# MCU.net
KiCad netlist of a schematic drawn in Altium Designer
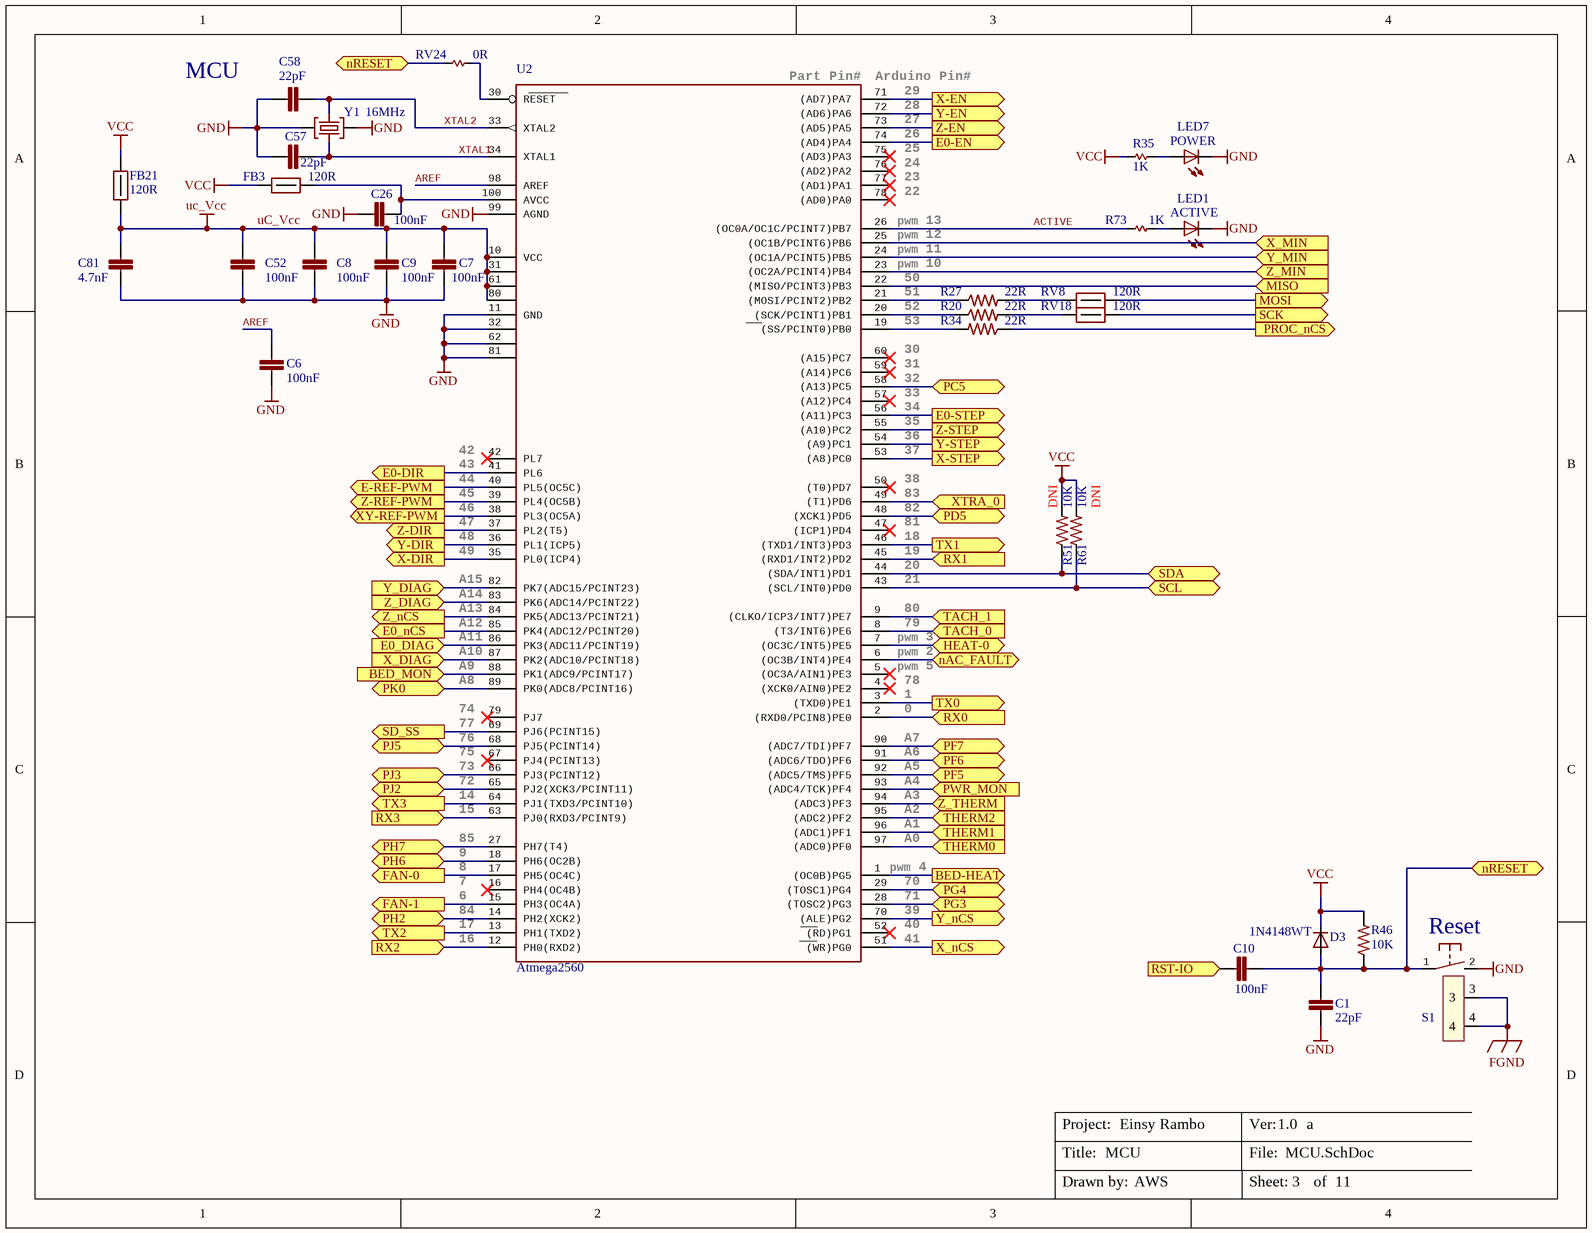
[diagram p0: MCU.SchDoc]

(export (version "E")
  (design (tool "Eeschema 10.0.6"))
  (components
    (comp (ref "C1")
      (value "22pF")
      (footprint "C0402")
      (description "CAP CER 0402 22pF 50V 5% C0G")
      (fields (field (name "MANUFACTURER") "AVX") (field (name "PART") "22pF 50V"))
      (libsource (lib "") (part "04025A220JAT2A_1"))
    )
    (comp (ref "C6")
      (value "100nF")
      (footprint "C0402")
      (description "CAP CER 0402 100nF 16V 10% X7R")
      (fields (field (name "MANUFACTURER") "Murata") (field (name "TOLERANCE") "+/- 10%"))
      (libsource (lib "3Delight") (part "GRM155R71C104KA88D"))
    )
    (comp (ref "C7")
      (value "100nF")
      (footprint "C0402")
      (description "CAP CER 0402 100nF 16V 10% X7R")
      (fields (field (name "MANUFACTURER") "Murata") (field (name "TOLERANCE") "+/- 10%"))
      (libsource (lib "3Delight") (part "GRM155R71C104KA88D"))
    )
    (comp (ref "C8")
      (value "100nF")
      (footprint "C0402")
      (description "CAP CER 0402 100nF 16V 10% X7R")
      (fields (field (name "MANUFACTURER") "Murata") (field (name "TOLERANCE") "+/- 10%"))
      (libsource (lib "3Delight") (part "GRM155R71C104KA88D"))
    )
    (comp (ref "C9")
      (value "100nF")
      (footprint "C0402")
      (description "CAP CER 0402 100nF 16V 10% X7R")
      (fields (field (name "MANUFACTURER") "Murata") (field (name "TOLERANCE") "+/- 10%"))
      (libsource (lib "3Delight") (part "GRM155R71C104KA88D"))
    )
    (comp (ref "C10")
      (value "100nF")
      (footprint "C0402")
      (description "CAP CER 0402 100nF 16V 10% X7R")
      (fields (field (name "MANUFACTURER") "Murata") (field (name "TOLERANCE") "+/- 10%"))
      (libsource (lib "") (part "GRM155R71C104KA88D_1"))
    )
    (comp (ref "C26")
      (value "100nF")
      (footprint "C0402")
      (description "CAP CER 0402 100nF 16V 10% X7R")
      (fields (field (name "MANUFACTURER") "Murata") (field (name "TOLERANCE") "+/- 10%"))
      (libsource (lib "") (part "GRM155R71C104KA88D_2"))
    )
    (comp (ref "C52")
      (value "100nF")
      (footprint "C0402")
      (description "CAP CER 0402 100nF 16V 10% X7R")
      (fields (field (name "MANUFACTURER") "Murata") (field (name "TOLERANCE") "+/- 10%"))
      (libsource (lib "3Delight") (part "GRM155R71C104KA88D"))
    )
    (comp (ref "C57")
      (value "22pF")
      (footprint "C0402")
      (description "CAP CER 0402 22pF 50V 5% C0G")
      (fields (field (name "MANUFACTURER") "AVX") (field (name "PART") "22pF 50V"))
      (libsource (lib "3Delight") (part "04025A220JAT2A"))
    )
    (comp (ref "C58")
      (value "22pF")
      (footprint "C0402")
      (description "CAP CER 0402 22pF 50V 5% C0G")
      (fields (field (name "MANUFACTURER") "AVX") (field (name "PART") "22pF 50V"))
      (libsource (lib "3Delight") (part "04025A220JAT2A"))
    )
    (comp (ref "C81")
      (value "4.7nF")
      (footprint "C0402")
      (description "CAP CER 0402 4.7nF 25V 10% X7R")
      (fields (field (name "MANUFACTURER") "YAGEO") (field (name "TOLERANCE") "+/- 10%"))
      (libsource (lib "3Delight") (part "CC0402KRX7R8BB472"))
    )
    (comp (ref "D3")
      (value "1N4148WT")
      (footprint "SOD523")
      (description "DIODE SOD523")
      (fields (field (name "MANUFACTURER") "Fairchild") (field (name "TOLERANCE") "NA"))
      (libsource (lib "3Delight") (part "1N4148WT"))
    )
    (comp (ref "FB3")
      (value "120R")
      (footprint "FB0603")
      (description "FERRITE BEAD 120 OHM 0603 1LN")
      (fields (field (name "MANUFACTURER") "Samsung") (field (name "PART") "FERRITE 120R 3A 0603"))
      (libsource (lib "3Delight") (part "FERRITE 220R 2.5A 0603"))
    )
    (comp (ref "FB21")
      (value "120R")
      (footprint "FB0603")
      (description "FERRITE BEAD 120 OHM 0603 1LN")
      (fields (field (name "MANUFACTURER") "Samsung") (field (name "PART") "FERRITE 120R 3A 0603"))
      (libsource (lib "Inductors") (part "FERRITE 120R 3A 0603"))
    )
    (comp (ref "LED1")
      (value "YEL")
      (footprint "LED2012120")
      (description "LED 0805 Yellow")
      (fields (field (name "MANUFACTURER") "Dialight") (field (name "TOLERANCE") "NA"))
      (libsource (lib "3Delight") (part "5988140107F"))
    )
    (comp (ref "LED7")
      (value "GRN")
      (footprint "LED2012120")
      (description "LED 0805 Green")
      (fields (field (name "MANUFACTURER") "Dialight") (field (name "TOLERANCE") "NA"))
      (libsource (lib "3Delight") (part "5988170107F"))
    )
    (comp (ref "R20")
      (value "22R")
      (footprint "R0402")
      (description "RES 0402 22r 62.5mW 1%")
      (fields (field (name "MANUFACTURER") "Yageo") (field (name "TOLERANCE") "+/- 1%"))
      (libsource (lib "3Delight") (part "RC0402FR-0722RL"))
    )
    (comp (ref "R27")
      (value "22R")
      (footprint "R0402")
      (description "RES 0402 22r 62.5mW 1%")
      (fields (field (name "MANUFACTURER") "Yageo") (field (name "TOLERANCE") "+/- 1%"))
      (libsource (lib "3Delight") (part "RC0402FR-0722RL"))
    )
    (comp (ref "R34")
      (value "22R")
      (footprint "R0402")
      (description "RES 0402 22r 62.5mW 1%")
      (fields (field (name "MANUFACTURER") "Yageo") (field (name "TOLERANCE") "+/- 1%"))
      (libsource (lib "3Delight") (part "RC0402FR-0722RL"))
    )
    (comp (ref "R35")
      (value "1K")
      (footprint "R0402")
      (description "RES SMD 1K OHM 1% 1/16W 0402")
      (fields (field (name "MANUFACTURER") "Yageo") (field (name "PART") "1k"))
      (libsource (lib "3Delight") (part "RC0402FR-071KL"))
    )
    (comp (ref "R46")
      (value "10K")
      (footprint "R0402")
      (description "RES SMD 10K OHM 1% 1/16W 0402")
      (fields (field (name "MANUFACTURER") "Yageo") (field (name "PART") "10k 1% 0402"))
      (libsource (lib "3Delight") (part "RC0402FR-0710KP"))
    )
    (comp (ref "R51")
      (value "10K")
      (footprint "R0402")
      (description "RES SMD 10K OHM 1% 1/16W 0402")
      (fields
        (field (name "MANUFACTURER") "Yageo")
        (field (name "PART") "10k 1% 0402")
        (field (name "DNI") "DNI")
      )
      (libsource (lib "3Delight") (part "RC0402FR-0710KP"))
    )
    (comp (ref "R61")
      (value "10K")
      (footprint "R0402")
      (description "RES SMD 10K OHM 1% 1/16W 0402")
      (fields
        (field (name "MANUFACTURER") "Yageo")
        (field (name "PART") "10k 1% 0402")
        (field (name "DNI") "DNI")
      )
      (libsource (lib "3Delight") (part "RC0402FR-0710KP"))
    )
    (comp (ref "R73")
      (value "1K")
      (footprint "R0402")
      (description "RES SMD 1K OHM 1% 1/16W 0402")
      (fields (field (name "MANUFACTURER") "Yageo") (field (name "PART") "1k"))
      (libsource (lib "3Delight") (part "RC0402FR-071KL"))
    )
    (comp (ref "RV8")
      (value "120R")
      (footprint "R0402")
      (description "FERRITE BEAD 120 OHM 0402 1LN")
      (fields (field (name "MANUFACTURER") "Taiyo Yuden") (field (name "PART") "FERRITE 120R 1A 0402"))
      (libsource (lib "Inductors") (part "FERRITE 120R 1A 0402"))
    )
    (comp (ref "RV18")
      (value "120R")
      (footprint "R0402")
      (description "FERRITE BEAD 120 OHM 0402 1LN")
      (fields (field (name "MANUFACTURER") "Taiyo Yuden") (field (name "PART") "FERRITE 120R 1A 0402"))
      (libsource (lib "Inductors") (part "FERRITE 120R 1A 0402"))
    )
    (comp (ref "RV24")
      (value "0R")
      (footprint "R0402")
      (description "RES SMD 0.0OHM JUMPER 1/10W 0402")
      (fields (field (name "MANUFACTURER") "Panasonic") (field (name "TOLERANCE") "1%"))
      (libsource (lib "Resistors") (part "0R 0402"))
    )
    (comp (ref "S1")
      (value "1571610-2")
      (footprint "B3F-31XX")
      (description "SWTCH Momentary Washable")
      (fields (field (name "MANUFACTURER") "TE") (field (name "PART") "Tact PB R/A"))
      (libsource (lib "3Delight") (part "1571610-2"))
    )
    (comp (ref "U2")
      (value "Atmega2560")
      (footprint "TSQFP50P1600X1600X120-100L")
      (fields
        (field (name "MANUFACTURER") "Microchip")
        (field (name "PART") "ATMEGA2560")
        (field (name "TOLERANCE") "NA")
      )
      (libsource (lib "ICs-uC") (part "ATMEGA2560AU_SM"))
    )
    (comp (ref "Y1")
      (value "16MHz")
      (footprint "CRYS320250")
      (description "Crystal 16mHz 10ppm 10pF")
      (fields (field (name "MANUFACTURER") "TXC") (field (name "TOLERANCE") "10ppm"))
      (libsource (lib "3Delight") (part "7M-16.000MEEQ-T"))
    )
  )
  (nets
    (net (code "1") (name "/ACTIVE") (class "Default")
      (node (ref "R73") (pin "2") (pinfunction "2_2") (pintype "passive"))
      (node (ref "U2") (pin "26") (pinfunction "(OC0A/OC1C/PCINT7)PB7_26") (pintype "passive"))
    )
    (net (code "2") (name "/AREF") (class "Default")
      (node (ref "C6") (pin "1") (pinfunction "1_1") (pintype "passive"))
      (node (ref "U2") (pin "98") (pinfunction "AREF_98") (pintype "passive"))
    )
    (net (code "3") (name "/BED-HEAT") (class "Default")
      (node (ref "U2") (pin "1") (pinfunction "(OC0B)PG5_1") (pintype "passive"))
    )
    (net (code "4") (name "/BED_MON") (class "Default")
      (node (ref "U2") (pin "88") (pinfunction "PK1(ADC9/PCINT17)_88") (pintype "passive"))
    )
    (net (code "5") (name "/E-REF-PWM") (class "Default")
      (node (ref "U2") (pin "40") (pinfunction "PL5(OC5C)_40") (pintype "passive"))
    )
    (net (code "6") (name "/E0-DIR") (class "Default")
      (node (ref "U2") (pin "41") (pinfunction "PL6_41") (pintype "passive"))
    )
    (net (code "7") (name "/E0-EN") (class "Default")
      (node (ref "U2") (pin "74") (pinfunction "(AD4)PA4_74") (pintype "passive"))
    )
    (net (code "8") (name "/E0-STEP") (class "Default")
      (node (ref "U2") (pin "56") (pinfunction "(A11)PC3_56") (pintype "passive"))
    )
    (net (code "9") (name "/E0_DIAG") (class "Default")
      (node (ref "U2") (pin "86") (pinfunction "PK3(ADC11/PCINT19)_86") (pintype "passive"))
    )
    (net (code "10") (name "/E0_nCS") (class "Default")
      (node (ref "U2") (pin "85") (pinfunction "PK4(ADC12/PCINT20)_85") (pintype "passive"))
    )
    (net (code "11") (name "/FAN-0") (class "Default")
      (node (ref "U2") (pin "17") (pinfunction "PH5(OC4C)_17") (pintype "passive"))
    )
    (net (code "12") (name "/FAN-1") (class "Default")
      (node (ref "U2") (pin "15") (pinfunction "PH3(OC4A)_15") (pintype "passive"))
    )
    (net (code "13") (name "/HEAT-0") (class "Default")
      (node (ref "U2") (pin "7") (pinfunction "(OC3C/INT5)PE5_7") (pintype "passive"))
    )
    (net (code "14") (name "/MISO") (class "Default")
      (node (ref "U2") (pin "22") (pinfunction "(MISO/PCINT3)PB3_22") (pintype "passive"))
    )
    (net (code "15") (name "/MOSI") (class "Default")
      (node (ref "RV8") (pin "2") (pinfunction "2_2") (pintype "passive"))
    )
    (net (code "16") (name "/PC5") (class "Default")
      (node (ref "U2") (pin "58") (pinfunction "(A13)PC5_58") (pintype "passive"))
    )
    (net (code "17") (name "/PD5") (class "Default")
      (node (ref "U2") (pin "48") (pinfunction "(XCK1)PD5_48") (pintype "passive"))
    )
    (net (code "18") (name "/PF5") (class "Default")
      (node (ref "U2") (pin "92") (pinfunction "(ADC5/TMS)PF5_92") (pintype "passive"))
    )
    (net (code "19") (name "/PF6") (class "Default")
      (node (ref "U2") (pin "91") (pinfunction "(ADC6/TDO)PF6_91") (pintype "passive"))
    )
    (net (code "20") (name "/PF7") (class "Default")
      (node (ref "U2") (pin "90") (pinfunction "(ADC7/TDI)PF7_90") (pintype "passive"))
    )
    (net (code "21") (name "/PG3") (class "Default")
      (node (ref "U2") (pin "28") (pinfunction "(TOSC2)PG3_28") (pintype "passive"))
    )
    (net (code "22") (name "/PG4") (class "Default")
      (node (ref "U2") (pin "29") (pinfunction "(TOSC1)PG4_29") (pintype "passive"))
    )
    (net (code "23") (name "/PH2") (class "Default")
      (node (ref "U2") (pin "14") (pinfunction "PH2(XCK2)_14") (pintype "passive"))
    )
    (net (code "24") (name "/PH6") (class "Default")
      (node (ref "U2") (pin "18") (pinfunction "PH6(OC2B)_18") (pintype "passive"))
    )
    (net (code "25") (name "/PH7") (class "Default")
      (node (ref "U2") (pin "27") (pinfunction "PH7(T4)_27") (pintype "passive"))
    )
    (net (code "26") (name "/PJ2") (class "Default")
      (node (ref "U2") (pin "65") (pinfunction "PJ2(XCK3/PCINT11)_65") (pintype "passive"))
    )
    (net (code "27") (name "/PJ3") (class "Default")
      (node (ref "U2") (pin "66") (pinfunction "PJ3(PCINT12)_66") (pintype "passive"))
    )
    (net (code "28") (name "/PJ5") (class "Default")
      (node (ref "U2") (pin "68") (pinfunction "PJ5(PCINT14)_68") (pintype "passive"))
    )
    (net (code "29") (name "/PK0") (class "Default")
      (node (ref "U2") (pin "89") (pinfunction "PK0(ADC8/PCINT16)_89") (pintype "passive"))
    )
    (net (code "30") (name "/PROC_nCS") (class "Default")
      (node (ref "R34") (pin "1") (pinfunction "1_1") (pintype "passive"))
    )
    (net (code "31") (name "/PWR_MON") (class "Default")
      (node (ref "U2") (pin "93") (pinfunction "(ADC4/TCK)PF4_93") (pintype "passive"))
    )
    (net (code "32") (name "/RST-IO") (class "Default")
      (node (ref "C10") (pin "1") (pinfunction "1_1") (pintype "passive"))
    )
    (net (code "33") (name "/RX0") (class "Default")
      (node (ref "U2") (pin "2") (pinfunction "(RXD0/PCIN8)PE0_2") (pintype "passive"))
    )
    (net (code "34") (name "/RX1") (class "Default")
      (node (ref "U2") (pin "45") (pinfunction "(RXD1/INT2)PD2_45") (pintype "passive"))
    )
    (net (code "35") (name "/RX2") (class "Default")
      (node (ref "U2") (pin "12") (pinfunction "PH0(RXD2)_12") (pintype "passive"))
    )
    (net (code "36") (name "/RX3") (class "Default")
      (node (ref "U2") (pin "63") (pinfunction "PJ0(RXD3/PCINT9)_63") (pintype "passive"))
    )
    (net (code "37") (name "/SCK") (class "Default")
      (node (ref "RV18") (pin "2") (pinfunction "2_2") (pintype "passive"))
    )
    (net (code "38") (name "/SCL") (class "Default")
      (node (ref "R61") (pin "1") (pinfunction "1_1") (pintype "passive"))
      (node (ref "U2") (pin "43") (pinfunction "(SCL/INT0)PD0_43") (pintype "passive"))
    )
    (net (code "39") (name "/SDA") (class "Default")
      (node (ref "R51") (pin "1") (pinfunction "1_1") (pintype "passive"))
      (node (ref "U2") (pin "44") (pinfunction "(SDA/INT1)PD1_44") (pintype "passive"))
    )
    (net (code "40") (name "/SD_SS") (class "Default")
      (node (ref "U2") (pin "69") (pinfunction "PJ6(PCINT15)_69") (pintype "passive"))
    )
    (net (code "41") (name "/TACH_0") (class "Default")
      (node (ref "U2") (pin "8") (pinfunction "(T3/INT6)PE6_8") (pintype "passive"))
    )
    (net (code "42") (name "/TACH_1") (class "Default")
      (node (ref "U2") (pin "9") (pinfunction "(CLKO/ICP3/INT7)PE7_9") (pintype "passive"))
    )
    (net (code "43") (name "/THERM0") (class "Default")
      (node (ref "U2") (pin "97") (pinfunction "(ADC0)PF0_97") (pintype "passive"))
    )
    (net (code "44") (name "/THERM1") (class "Default")
      (node (ref "U2") (pin "96") (pinfunction "(ADC1)PF1_96") (pintype "passive"))
    )
    (net (code "45") (name "/THERM2") (class "Default")
      (node (ref "U2") (pin "95") (pinfunction "(ADC2)PF2_95") (pintype "passive"))
    )
    (net (code "46") (name "/TX0") (class "Default")
      (node (ref "U2") (pin "3") (pinfunction "(TXD0)PE1_3") (pintype "passive"))
    )
    (net (code "47") (name "/TX1") (class "Default")
      (node (ref "U2") (pin "46") (pinfunction "(TXD1/INT3)PD3_46") (pintype "passive"))
    )
    (net (code "48") (name "/TX2") (class "Default")
      (node (ref "U2") (pin "13") (pinfunction "PH1(TXD2)_13") (pintype "passive"))
    )
    (net (code "49") (name "/TX3") (class "Default")
      (node (ref "U2") (pin "64") (pinfunction "PJ1(TXD3/PCINT10)_64") (pintype "passive"))
    )
    (net (code "50") (name "/X-DIR") (class "Default")
      (node (ref "U2") (pin "35") (pinfunction "PL0(ICP4)_35") (pintype "passive"))
    )
    (net (code "51") (name "/X-EN") (class "Default")
      (node (ref "U2") (pin "71") (pinfunction "(AD7)PA7_71") (pintype "passive"))
    )
    (net (code "52") (name "/X-STEP") (class "Default")
      (node (ref "U2") (pin "53") (pinfunction "(A8)PC0_53") (pintype "passive"))
    )
    (net (code "53") (name "/XTAL1") (class "Default")
      (node (ref "C57") (pin "1") (pinfunction "1_1") (pintype "passive"))
      (node (ref "U2") (pin "34") (pinfunction "XTAL1_34") (pintype "passive"))
      (node (ref "Y1") (pin "1") (pinfunction "C1_1") (pintype "passive"))
    )
    (net (code "54") (name "/XTAL2") (class "Default")
      (node (ref "C58") (pin "1") (pinfunction "1_1") (pintype "passive"))
      (node (ref "U2") (pin "33") (pinfunction "XTAL2_33") (pintype "output"))
      (node (ref "Y1") (pin "3") (pinfunction "C2_3") (pintype "passive"))
    )
    (net (code "55") (name "/XTRA_0") (class "Default")
      (node (ref "U2") (pin "49") (pinfunction "(T1)PD6_49") (pintype "passive"))
    )
    (net (code "56") (name "/XY-REF-PWM") (class "Default")
      (node (ref "U2") (pin "38") (pinfunction "PL3(OC5A)_38") (pintype "passive"))
    )
    (net (code "57") (name "/X_DIAG") (class "Default")
      (node (ref "U2") (pin "87") (pinfunction "PK2(ADC10/PCINT18)_87") (pintype "passive"))
    )
    (net (code "58") (name "/X_MIN") (class "Default")
      (node (ref "U2") (pin "25") (pinfunction "(OC1B/PCINT6)PB6_25") (pintype "passive"))
    )
    (net (code "59") (name "/X_nCS") (class "Default")
      (node (ref "U2") (pin "51") (pinfunction "(WR)PG0_51") (pintype "passive"))
    )
    (net (code "60") (name "/Y-DIR") (class "Default")
      (node (ref "U2") (pin "36") (pinfunction "PL1(ICP5)_36") (pintype "passive"))
    )
    (net (code "61") (name "/Y-EN") (class "Default")
      (node (ref "U2") (pin "72") (pinfunction "(AD6)PA6_72") (pintype "passive"))
    )
    (net (code "62") (name "/Y-STEP") (class "Default")
      (node (ref "U2") (pin "54") (pinfunction "(A9)PC1_54") (pintype "passive"))
    )
    (net (code "63") (name "/Y_DIAG") (class "Default")
      (node (ref "U2") (pin "82") (pinfunction "PK7(ADC15/PCINT23)_82") (pintype "passive"))
    )
    (net (code "64") (name "/Y_MIN") (class "Default")
      (node (ref "U2") (pin "24") (pinfunction "(OC1A/PCINT5)PB5_24") (pintype "passive"))
    )
    (net (code "65") (name "/Y_nCS") (class "Default")
      (node (ref "U2") (pin "70") (pinfunction "(ALE)PG2_70") (pintype "passive"))
    )
    (net (code "66") (name "/Z-DIR") (class "Default")
      (node (ref "U2") (pin "37") (pinfunction "PL2(T5)_37") (pintype "passive"))
    )
    (net (code "67") (name "/Z-EN") (class "Default")
      (node (ref "U2") (pin "73") (pinfunction "(AD5)PA5_73") (pintype "passive"))
    )
    (net (code "68") (name "/Z-REF-PWM") (class "Default")
      (node (ref "U2") (pin "39") (pinfunction "PL4(OC5B)_39") (pintype "passive"))
    )
    (net (code "69") (name "/Z-STEP") (class "Default")
      (node (ref "U2") (pin "55") (pinfunction "(A10)PC2_55") (pintype "passive"))
    )
    (net (code "70") (name "/Z_DIAG") (class "Default")
      (node (ref "U2") (pin "83") (pinfunction "PK6(ADC14/PCINT22)_83") (pintype "passive"))
    )
    (net (code "71") (name "/Z_MIN") (class "Default")
      (node (ref "U2") (pin "23") (pinfunction "(OC2A/PCINT4)PB4_23") (pintype "passive"))
    )
    (net (code "72") (name "/Z_THERM") (class "Default")
      (node (ref "U2") (pin "94") (pinfunction "(ADC3)PF3_94") (pintype "passive"))
    )
    (net (code "73") (name "/Z_nCS") (class "Default")
      (node (ref "U2") (pin "84") (pinfunction "PK5(ADC13/PCINT21)_84") (pintype "passive"))
    )
    (net (code "74") (name "/nAC_FAULT") (class "Default")
      (node (ref "U2") (pin "6") (pinfunction "(OC3B/INT4)PE4_6") (pintype "passive"))
    )
    (net (code "75") (name "/nRESET") (class "Default")
      (node (ref "C1") (pin "1") (pinfunction "1_1") (pintype "passive"))
      (node (ref "C10") (pin "2") (pinfunction "2_2") (pintype "passive"))
      (node (ref "D3") (pin "A") (pinfunction "A_A") (pintype "passive"))
      (node (ref "R46") (pin "1") (pinfunction "1_1") (pintype "passive"))
      (node (ref "RV24") (pin "1") (pinfunction "1_1") (pintype "passive"))
      (node (ref "S1") (pin "1") (pinfunction "P_1") (pintype "passive"))
    )
    (net (code "76") (name "FGND") (class "Default")
      (node (ref "S1") (pin "3") (pinfunction "3_3") (pintype "power_in"))
      (node (ref "S1") (pin "4") (pinfunction "4_4") (pintype "power_in"))
    )
    (net (code "77") (name "GND") (class "Default")
      (node (ref "C1") (pin "2") (pinfunction "2_2") (pintype "passive"))
      (node (ref "C26") (pin "2") (pinfunction "2_2") (pintype "passive"))
      (node (ref "C52") (pin "2") (pinfunction "2_2") (pintype "passive"))
      (node (ref "C57") (pin "2") (pinfunction "2_2") (pintype "passive"))
      (node (ref "C58") (pin "2") (pinfunction "2_2") (pintype "passive"))
      (node (ref "C6") (pin "2") (pinfunction "2_2") (pintype "passive"))
      (node (ref "C7") (pin "2") (pinfunction "2_2") (pintype "passive"))
      (node (ref "C8") (pin "2") (pinfunction "2_2") (pintype "passive"))
      (node (ref "C81") (pin "2") (pinfunction "2_2") (pintype "passive"))
      (node (ref "C9") (pin "2") (pinfunction "2_2") (pintype "passive"))
      (node (ref "LED1") (pin "C") (pinfunction "C_C") (pintype "passive"))
      (node (ref "LED7") (pin "C") (pinfunction "C_C") (pintype "passive"))
      (node (ref "S1") (pin "2") (pinfunction "S_2") (pintype "passive"))
      (node (ref "U2") (pin "11") (pinfunction "GND_11") (pintype "power_in"))
      (node (ref "U2") (pin "32") (pinfunction "GND1_32") (pintype "power_in"))
      (node (ref "U2") (pin "62") (pinfunction "GND2_62") (pintype "power_in"))
      (node (ref "U2") (pin "81") (pinfunction "GND3_81") (pintype "power_in"))
      (node (ref "U2") (pin "99") (pinfunction "AGND_99") (pintype "power_in"))
      (node (ref "Y1") (pin "2") (pinfunction "GND_2") (pintype "passive"))
      (node (ref "Y1") (pin "4") (pinfunction "GND_4") (pintype "passive"))
    )
    (net (code "78") (name "Net-(LED1-PadA)") (class "Default")
      (node (ref "LED1") (pin "A") (pinfunction "A_A") (pintype "passive"))
      (node (ref "R73") (pin "1") (pinfunction "1_1") (pintype "passive"))
    )
    (net (code "79") (name "Net-(LED7-PadA)") (class "Default")
      (node (ref "LED7") (pin "A") (pinfunction "A_A") (pintype "passive"))
      (node (ref "R35") (pin "1") (pinfunction "1_1") (pintype "passive"))
    )
    (net (code "80") (name "Net-(R20-Pad2)") (class "Default")
      (node (ref "R20") (pin "2") (pinfunction "2_2") (pintype "passive"))
      (node (ref "RV18") (pin "1") (pinfunction "1_1") (pintype "passive"))
    )
    (net (code "81") (name "Net-(R27-Pad2)") (class "Default")
      (node (ref "R27") (pin "2") (pinfunction "2_2") (pintype "passive"))
      (node (ref "RV8") (pin "1") (pinfunction "1_1") (pintype "passive"))
    )
    (net (code "82") (name "Net-(U2-(MOSI{slash}PCINT2)PB2)") (class "Default")
      (node (ref "R27") (pin "1") (pinfunction "1_1") (pintype "passive"))
      (node (ref "U2") (pin "21") (pinfunction "(MOSI/PCINT2)PB2_21") (pintype "passive"))
    )
    (net (code "83") (name "Net-(U2-(SCK{slash}PCINT1)PB1)") (class "Default")
      (node (ref "R20") (pin "1") (pinfunction "1_1") (pintype "passive"))
      (node (ref "U2") (pin "20") (pinfunction "(SCK/PCINT1)PB1_20") (pintype "passive"))
    )
    (net (code "84") (name "Net-(U2-(SS{slash}PCINT0)PB0)") (class "Default")
      (node (ref "R34") (pin "2") (pinfunction "2_2") (pintype "passive"))
      (node (ref "U2") (pin "19") (pinfunction "(SS/PCINT0)PB0_19") (pintype "passive"))
    )
    (net (code "85") (name "Net-(U2-AVCC)") (class "Default")
      (node (ref "C26") (pin "1") (pinfunction "1_1") (pintype "passive"))
      (node (ref "FB3") (pin "2") (pinfunction "2_2") (pintype "passive"))
      (node (ref "U2") (pin "100") (pinfunction "AVCC_100") (pintype "power_in"))
    )
    (net (code "86") (name "Net-(U2-RESET)") (class "Default")
      (node (ref "RV24") (pin "2") (pinfunction "2_2") (pintype "passive"))
      (node (ref "U2") (pin "30") (pinfunction "RESET_30") (pintype "passive"))
    )
    (net (code "87") (name "VCC") (class "Default")
      (node (ref "D3") (pin "C") (pinfunction "C_C") (pintype "passive"))
      (node (ref "FB21") (pin "1") (pinfunction "1_1") (pintype "passive"))
      (node (ref "FB3") (pin "1") (pinfunction "1_1") (pintype "passive"))
      (node (ref "R35") (pin "2") (pinfunction "2_2") (pintype "passive"))
      (node (ref "R46") (pin "2") (pinfunction "2_2") (pintype "passive"))
      (node (ref "R51") (pin "2") (pinfunction "2_2") (pintype "passive"))
      (node (ref "R61") (pin "2") (pinfunction "2_2") (pintype "passive"))
    )
    (net (code "88") (name "uc_Vcc") (class "Default")
      (node (ref "C52") (pin "1") (pinfunction "1_1") (pintype "passive"))
      (node (ref "C7") (pin "1") (pinfunction "1_1") (pintype "passive"))
      (node (ref "C8") (pin "1") (pinfunction "1_1") (pintype "passive"))
      (node (ref "C81") (pin "1") (pinfunction "1_1") (pintype "passive"))
      (node (ref "C9") (pin "1") (pinfunction "1_1") (pintype "passive"))
      (node (ref "FB21") (pin "2") (pinfunction "2_2") (pintype "passive"))
      (node (ref "U2") (pin "10") (pinfunction "VCC_10") (pintype "power_in"))
      (node (ref "U2") (pin "31") (pinfunction "VCC1_31") (pintype "power_in"))
      (node (ref "U2") (pin "61") (pinfunction "VCC2_61") (pintype "power_in"))
      (node (ref "U2") (pin "80") (pinfunction "VCC3_80") (pintype "power_in"))
    )
    (net (code "89") (name "unconnected-(U2-(A12)PC4-Pad57)") (class "Default")
      (node (ref "U2") (pin "57") (pinfunction "(A12)PC4_57") (pintype "passive+no_connect"))
    )
    (net (code "90") (name "unconnected-(U2-(A14)PC6-Pad59)") (class "Default")
      (node (ref "U2") (pin "59") (pinfunction "(A14)PC6_59") (pintype "passive+no_connect"))
    )
    (net (code "91") (name "unconnected-(U2-(A15)PC7-Pad60)") (class "Default")
      (node (ref "U2") (pin "60") (pinfunction "(A15)PC7_60") (pintype "passive+no_connect"))
    )
    (net (code "92") (name "unconnected-(U2-(AD0)PA0-Pad78)") (class "Default")
      (node (ref "U2") (pin "78") (pinfunction "(AD0)PA0_78") (pintype "passive+no_connect"))
    )
    (net (code "93") (name "unconnected-(U2-(AD1)PA1-Pad77)") (class "Default")
      (node (ref "U2") (pin "77") (pinfunction "(AD1)PA1_77") (pintype "passive+no_connect"))
    )
    (net (code "94") (name "unconnected-(U2-(AD2)PA2-Pad76)") (class "Default")
      (node (ref "U2") (pin "76") (pinfunction "(AD2)PA2_76") (pintype "passive+no_connect"))
    )
    (net (code "95") (name "unconnected-(U2-(AD3)PA3-Pad75)") (class "Default")
      (node (ref "U2") (pin "75") (pinfunction "(AD3)PA3_75") (pintype "passive+no_connect"))
    )
    (net (code "96") (name "unconnected-(U2-(ICP1)PD4-Pad47)") (class "Default")
      (node (ref "U2") (pin "47") (pinfunction "(ICP1)PD4_47") (pintype "passive+no_connect"))
    )
    (net (code "97") (name "unconnected-(U2-(OC3A{slash}AIN1)PE3-Pad5)") (class "Default")
      (node (ref "U2") (pin "5") (pinfunction "(OC3A/AIN1)PE3_5") (pintype "passive+no_connect"))
    )
    (net (code "98") (name "unconnected-(U2-(RD)PG1-Pad52)") (class "Default")
      (node (ref "U2") (pin "52") (pinfunction "(RD)PG1_52") (pintype "passive+no_connect"))
    )
    (net (code "99") (name "unconnected-(U2-(T0)PD7-Pad50)") (class "Default")
      (node (ref "U2") (pin "50") (pinfunction "(T0)PD7_50") (pintype "passive+no_connect"))
    )
    (net (code "100") (name "unconnected-(U2-(XCK0{slash}AIN0)PE2-Pad4)") (class "Default")
      (node (ref "U2") (pin "4") (pinfunction "(XCK0/AIN0)PE2_4") (pintype "passive+no_connect"))
    )
    (net (code "101") (name "unconnected-(U2-PH4(OC4B)-Pad16)") (class "Default")
      (node (ref "U2") (pin "16") (pinfunction "PH4(OC4B)_16") (pintype "passive+no_connect"))
    )
    (net (code "102") (name "unconnected-(U2-PJ4(PCINT13)-Pad67)") (class "Default")
      (node (ref "U2") (pin "67") (pinfunction "PJ4(PCINT13)_67") (pintype "passive+no_connect"))
    )
    (net (code "103") (name "unconnected-(U2-PJ7-Pad79)") (class "Default")
      (node (ref "U2") (pin "79") (pinfunction "PJ7_79") (pintype "passive+no_connect"))
    )
    (net (code "104") (name "unconnected-(U2-PL7-Pad42)") (class "Default")
      (node (ref "U2") (pin "42") (pinfunction "PL7_42") (pintype "passive+no_connect"))
    )
  )
)
